# schematic.net
KiCad netlist of a schematic drawn in Altium Designer
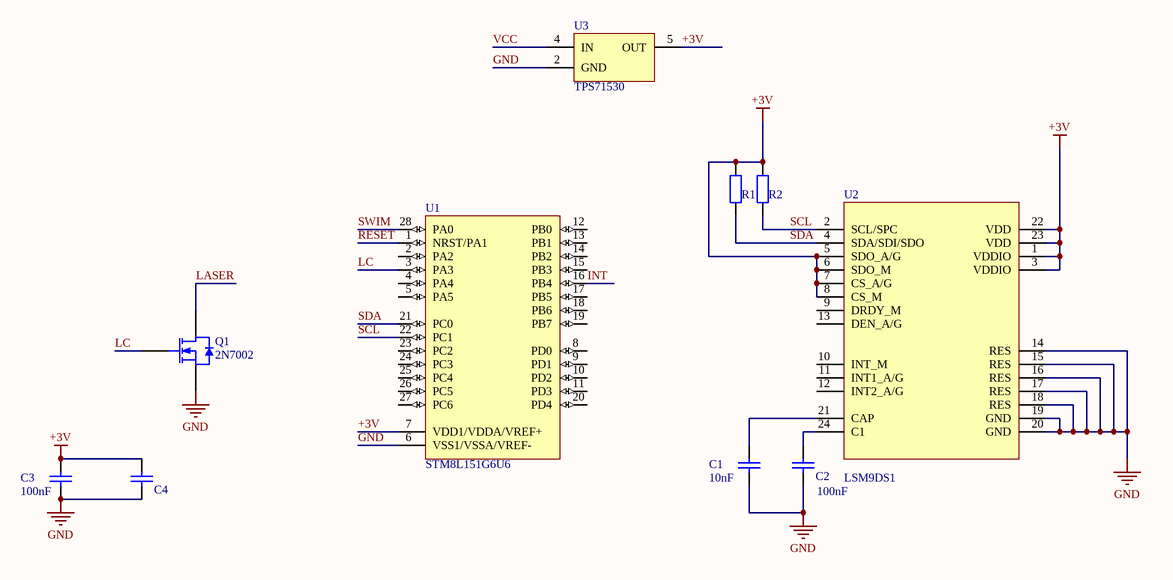
[diagram p0: schematic.SchDoc]

(export (version "E")
  (design (tool "Eeschema 10.0.6"))
  (components
    (comp (ref "C1")
      (value "C0603")
      (footprint "CAPC1608N")
      (description "Конденсатор")
      (fields (field (name "НОМИНАЛ") "10nF"))
      (libsource (lib "BHL_Compass") (part "C0603"))
    )
    (comp (ref "C2")
      (value "C0603")
      (footprint "CAPC1005N")
      (description "Конденсатор")
      (fields (field (name "НОМИНАЛ") "100nF"))
      (libsource (lib "BHL_Compass") (part "C0603"))
    )
    (comp (ref "C3")
      (value "C0603")
      (footprint "CAPC1005N")
      (description "Конденсатор")
      (fields (field (name "НОМИНАЛ") "100nF"))
      (libsource (lib "BHL_Compass") (part "C0603"))
    )
    (comp (ref "C4")
      (value "C0603")
      (footprint "CAPC1608N")
      (description "Конденсатор")
      (libsource (lib "BHL_Compass") (part "C0603"))
    )
    (comp (ref "Q1")
      (value "2N7002")
      (footprint "SOT23-3L")
      (description "N-channel Enhancement Mode Field-effect Transistor")
      (fields (field (name "PUBLISHER") "Altium Limited"))
      (libsource (lib "BHL_Compass") (part "2N7002"))
    )
    (comp (ref "R1")
      (value "R0603")
      (footprint "RESC1005N")
      (description "Резистор")
      (libsource (lib "BHL_Compass") (part "R0603"))
    )
    (comp (ref "R2")
      (value "R0603")
      (footprint "RESC1005N")
      (description "Резистор")
      (libsource (lib "BHL_Compass") (part "R0603"))
    )
    (comp (ref "U1")
      (value "STM8L151G6U6")
      (footprint "UFQFPN28_V")
      (libsource (lib "STMicroelectronics STM8L") (part "STM8L151G6U6"))
    )
    (comp (ref "U2")
      (value "LSM9DS1")
      (footprint "QFN43P350X300X100-24M")
      (description "iNEMO digital compass")
      (libsource (lib "BHL_Compass") (part "LSM9DS1"))
    )
    (comp (ref "U3")
      (value "TPS71530")
      (footprint "TSOP65P210X50-5N")
      (description "Стабилизатор")
      (libsource (lib "BHL_Compass") (part "TPS71530"))
    )
  )
  (nets
    (net (code "1") (name "+3V") (class "Default")
      (node (ref "C3") (pin "2") (pinfunction "2_2") (pintype "passive"))
      (node (ref "C4") (pin "2") (pinfunction "2_2") (pintype "passive"))
      (node (ref "R1") (pin "1") (pinfunction "1_1") (pintype "passive"))
      (node (ref "R2") (pin "1") (pinfunction "1_1") (pintype "passive"))
      (node (ref "U1") (pin "7") (pinfunction "VDD1/VDDA/VREF+_7") (pintype "power_in"))
      (node (ref "U2") (pin "1") (pinfunction "VDDIO_1") (pintype "passive"))
      (node (ref "U2") (pin "22") (pinfunction "VDD_22") (pintype "passive"))
      (node (ref "U2") (pin "23") (pinfunction "VDD_23") (pintype "passive"))
      (node (ref "U2") (pin "3") (pinfunction "VDDIO_3") (pintype "passive"))
      (node (ref "U2") (pin "5") (pinfunction "SDO_A/G_5") (pintype "passive"))
      (node (ref "U2") (pin "6") (pinfunction "SDO_M_6") (pintype "passive"))
      (node (ref "U2") (pin "7") (pinfunction "CS_A/G_7") (pintype "passive"))
      (node (ref "U2") (pin "8") (pinfunction "CS_M_8") (pintype "passive"))
      (node (ref "U3") (pin "5") (pinfunction "OUT_5") (pintype "passive"))
    )
    (net (code "2") (name "/INT") (class "Default")
      (node (ref "U1") (pin "16") (pinfunction "PB4_16") (pintype "bidirectional"))
    )
    (net (code "3") (name "/LASER") (class "Default")
      (node (ref "Q1") (pin "3") (pinfunction "D_3") (pintype "passive"))
    )
    (net (code "4") (name "/LC") (class "Default")
      (node (ref "Q1") (pin "1") (pinfunction "G_1") (pintype "passive"))
      (node (ref "U1") (pin "3") (pinfunction "PA3_3") (pintype "bidirectional"))
    )
    (net (code "5") (name "/RESET") (class "Default")
      (node (ref "U1") (pin "1") (pinfunction "NRST/PA1_1") (pintype "bidirectional"))
    )
    (net (code "6") (name "/SCL") (class "Default")
      (node (ref "R2") (pin "2") (pinfunction "2_2") (pintype "passive"))
      (node (ref "U1") (pin "22") (pinfunction "PC1_22") (pintype "bidirectional"))
      (node (ref "U2") (pin "2") (pinfunction "SCL/SPC_2") (pintype "passive"))
    )
    (net (code "7") (name "/SDA") (class "Default")
      (node (ref "R1") (pin "2") (pinfunction "2_2") (pintype "passive"))
      (node (ref "U1") (pin "21") (pinfunction "PC0_21") (pintype "bidirectional"))
      (node (ref "U2") (pin "4") (pinfunction "SDA/SDI/SDO_4") (pintype "passive"))
    )
    (net (code "8") (name "/SWIM") (class "Default")
      (node (ref "U1") (pin "28") (pinfunction "PA0_28") (pintype "bidirectional"))
    )
    (net (code "9") (name "/VCC") (class "Default")
      (node (ref "U3") (pin "4") (pinfunction "IN_4") (pintype "passive"))
    )
    (net (code "10") (name "GND") (class "Default")
      (node (ref "C1") (pin "1") (pinfunction "1_1") (pintype "passive"))
      (node (ref "C2") (pin "1") (pinfunction "1_1") (pintype "passive"))
      (node (ref "C3") (pin "1") (pinfunction "1_1") (pintype "passive"))
      (node (ref "C4") (pin "1") (pinfunction "1_1") (pintype "passive"))
      (node (ref "Q1") (pin "2") (pinfunction "S_2") (pintype "passive"))
      (node (ref "U1") (pin "6") (pinfunction "VSS1/VSSA/VREF-_6") (pintype "power_in"))
      (node (ref "U2") (pin "14") (pinfunction "RES_14") (pintype "passive"))
      (node (ref "U2") (pin "15") (pinfunction "RES_15") (pintype "passive"))
      (node (ref "U2") (pin "16") (pinfunction "RES_16") (pintype "passive"))
      (node (ref "U2") (pin "17") (pinfunction "RES_17") (pintype "passive"))
      (node (ref "U2") (pin "18") (pinfunction "RES_18") (pintype "passive"))
      (node (ref "U2") (pin "19") (pinfunction "GND_19") (pintype "passive"))
      (node (ref "U2") (pin "20") (pinfunction "GND_20") (pintype "passive"))
      (node (ref "U3") (pin "2") (pinfunction "GND_2") (pintype "passive"))
    )
    (net (code "11") (name "Net-(U2-C1)") (class "Default")
      (node (ref "C2") (pin "2") (pinfunction "2_2") (pintype "passive"))
      (node (ref "U2") (pin "24") (pinfunction "C1_24") (pintype "passive"))
    )
    (net (code "12") (name "Net-(U2-CAP)") (class "Default")
      (node (ref "C1") (pin "2") (pinfunction "2_2") (pintype "passive"))
      (node (ref "U2") (pin "21") (pinfunction "CAP_21") (pintype "passive"))
    )
    (net (code "13") (name "unconnected-(U1-PA2-Pad2)") (class "Default")
      (node (ref "U1") (pin "2") (pinfunction "PA2_2") (pintype "bidirectional"))
    )
    (net (code "14") (name "unconnected-(U1-PA4-Pad4)") (class "Default")
      (node (ref "U1") (pin "4") (pinfunction "PA4_4") (pintype "bidirectional"))
    )
    (net (code "15") (name "unconnected-(U1-PA5-Pad5)") (class "Default")
      (node (ref "U1") (pin "5") (pinfunction "PA5_5") (pintype "bidirectional"))
    )
    (net (code "16") (name "unconnected-(U1-PB0-Pad12)") (class "Default")
      (node (ref "U1") (pin "12") (pinfunction "PB0_12") (pintype "bidirectional"))
    )
    (net (code "17") (name "unconnected-(U1-PB1-Pad13)") (class "Default")
      (node (ref "U1") (pin "13") (pinfunction "PB1_13") (pintype "bidirectional"))
    )
    (net (code "18") (name "unconnected-(U1-PB2-Pad14)") (class "Default")
      (node (ref "U1") (pin "14") (pinfunction "PB2_14") (pintype "bidirectional"))
    )
    (net (code "19") (name "unconnected-(U1-PB3-Pad15)") (class "Default")
      (node (ref "U1") (pin "15") (pinfunction "PB3_15") (pintype "bidirectional"))
    )
    (net (code "20") (name "unconnected-(U1-PB5-Pad17)") (class "Default")
      (node (ref "U1") (pin "17") (pinfunction "PB5_17") (pintype "bidirectional"))
    )
    (net (code "21") (name "unconnected-(U1-PB6-Pad18)") (class "Default")
      (node (ref "U1") (pin "18") (pinfunction "PB6_18") (pintype "bidirectional"))
    )
    (net (code "22") (name "unconnected-(U1-PB7-Pad19)") (class "Default")
      (node (ref "U1") (pin "19") (pinfunction "PB7_19") (pintype "bidirectional"))
    )
    (net (code "23") (name "unconnected-(U1-PC2-Pad23)") (class "Default")
      (node (ref "U1") (pin "23") (pinfunction "PC2_23") (pintype "bidirectional"))
    )
    (net (code "24") (name "unconnected-(U1-PC3-Pad24)") (class "Default")
      (node (ref "U1") (pin "24") (pinfunction "PC3_24") (pintype "bidirectional"))
    )
    (net (code "25") (name "unconnected-(U1-PC4-Pad25)") (class "Default")
      (node (ref "U1") (pin "25") (pinfunction "PC4_25") (pintype "bidirectional"))
    )
    (net (code "26") (name "unconnected-(U1-PC5-Pad26)") (class "Default")
      (node (ref "U1") (pin "26") (pinfunction "PC5_26") (pintype "bidirectional"))
    )
    (net (code "27") (name "unconnected-(U1-PC6-Pad27)") (class "Default")
      (node (ref "U1") (pin "27") (pinfunction "PC6_27") (pintype "bidirectional"))
    )
    (net (code "28") (name "unconnected-(U1-PD0-Pad8)") (class "Default")
      (node (ref "U1") (pin "8") (pinfunction "PD0_8") (pintype "bidirectional"))
    )
    (net (code "29") (name "unconnected-(U1-PD1-Pad9)") (class "Default")
      (node (ref "U1") (pin "9") (pinfunction "PD1_9") (pintype "bidirectional"))
    )
    (net (code "30") (name "unconnected-(U1-PD2-Pad10)") (class "Default")
      (node (ref "U1") (pin "10") (pinfunction "PD2_10") (pintype "bidirectional"))
    )
    (net (code "31") (name "unconnected-(U1-PD3-Pad11)") (class "Default")
      (node (ref "U1") (pin "11") (pinfunction "PD3_11") (pintype "bidirectional"))
    )
    (net (code "32") (name "unconnected-(U1-PD4-Pad20)") (class "Default")
      (node (ref "U1") (pin "20") (pinfunction "PD4_20") (pintype "bidirectional"))
    )
    (net (code "33") (name "unconnected-(U2-DEN_A{slash}G-Pad13)") (class "Default")
      (node (ref "U2") (pin "13") (pinfunction "DEN_A/G_13") (pintype "passive"))
    )
    (net (code "34") (name "unconnected-(U2-DRDY_M-Pad9)") (class "Default")
      (node (ref "U2") (pin "9") (pinfunction "DRDY_M_9") (pintype "passive"))
    )
    (net (code "35") (name "unconnected-(U2-INT1_A{slash}G-Pad11)") (class "Default")
      (node (ref "U2") (pin "11") (pinfunction "INT1_A/G_11") (pintype "passive"))
    )
    (net (code "36") (name "unconnected-(U2-INT2_A{slash}G-Pad12)") (class "Default")
      (node (ref "U2") (pin "12") (pinfunction "INT2_A/G_12") (pintype "passive"))
    )
    (net (code "37") (name "unconnected-(U2-INT_M-Pad10)") (class "Default")
      (node (ref "U2") (pin "10") (pinfunction "INT_M_10") (pintype "passive"))
    )
  )
)
